# ProPrj_PASSMAN_BLE_Fingerprint_V1_2025-0.net
KiCad netlist of a schematic drawn in EasyEDA Pro
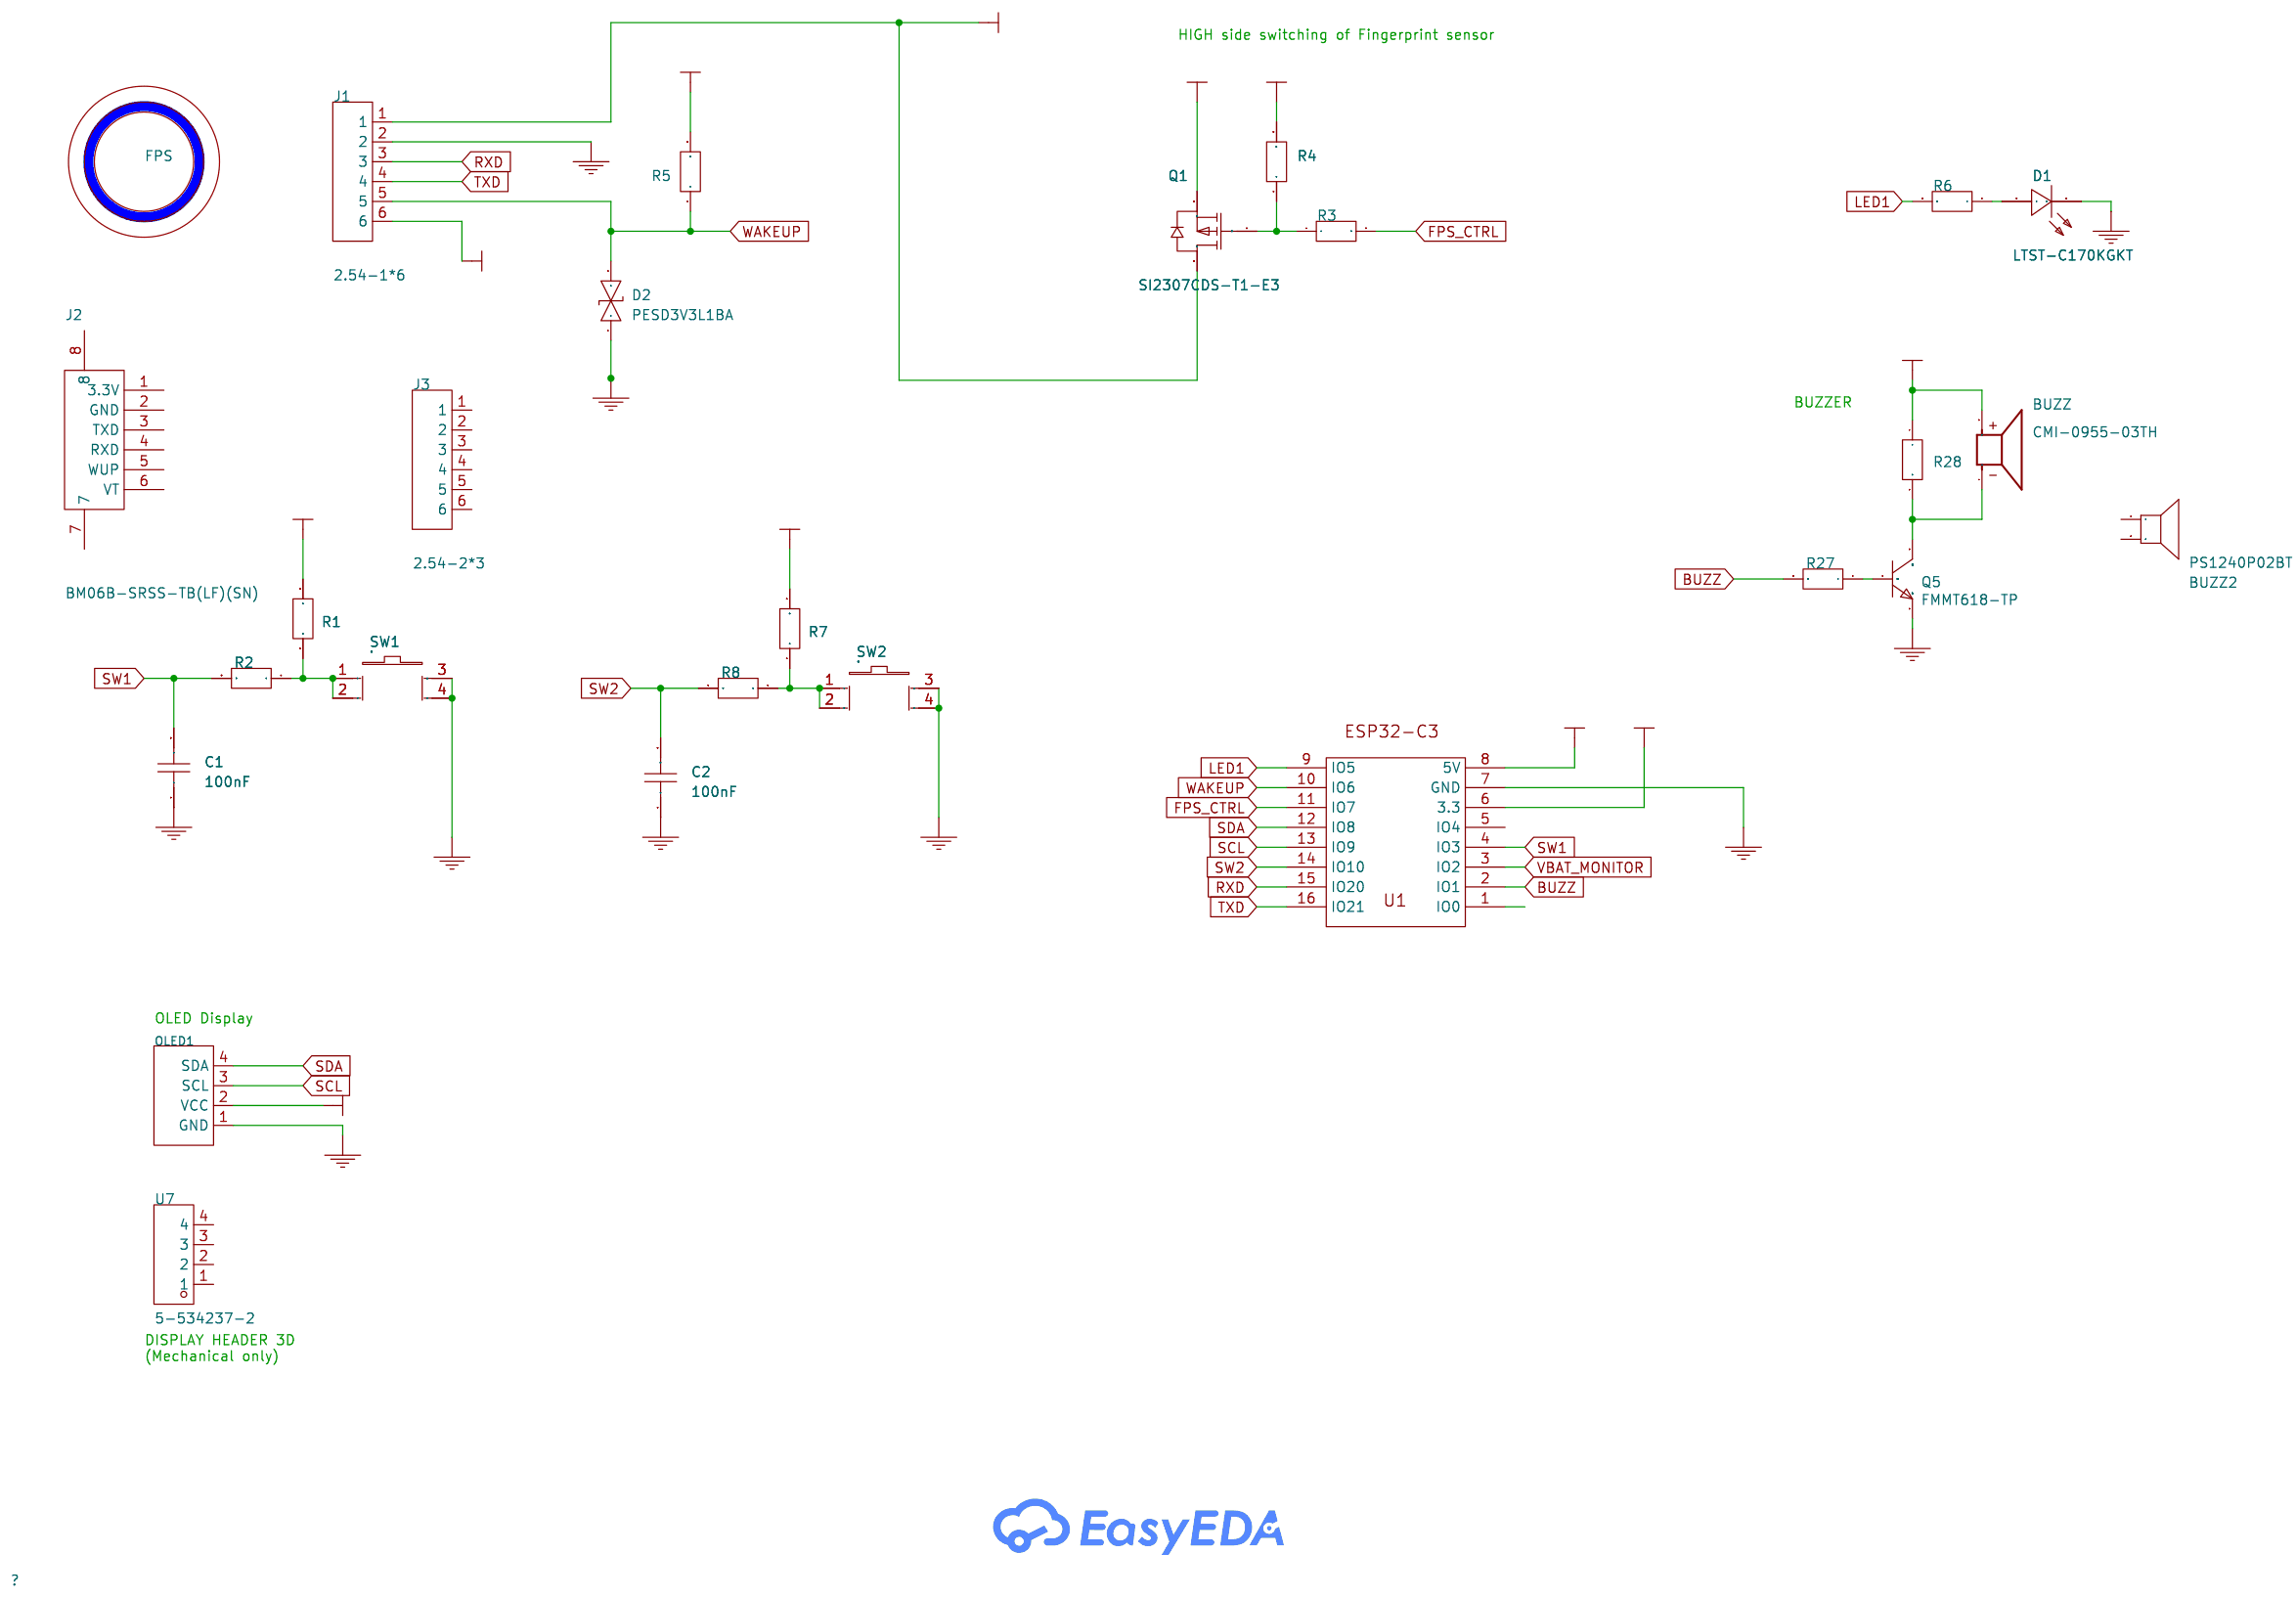
[diagram p0: ESP32 Mini]
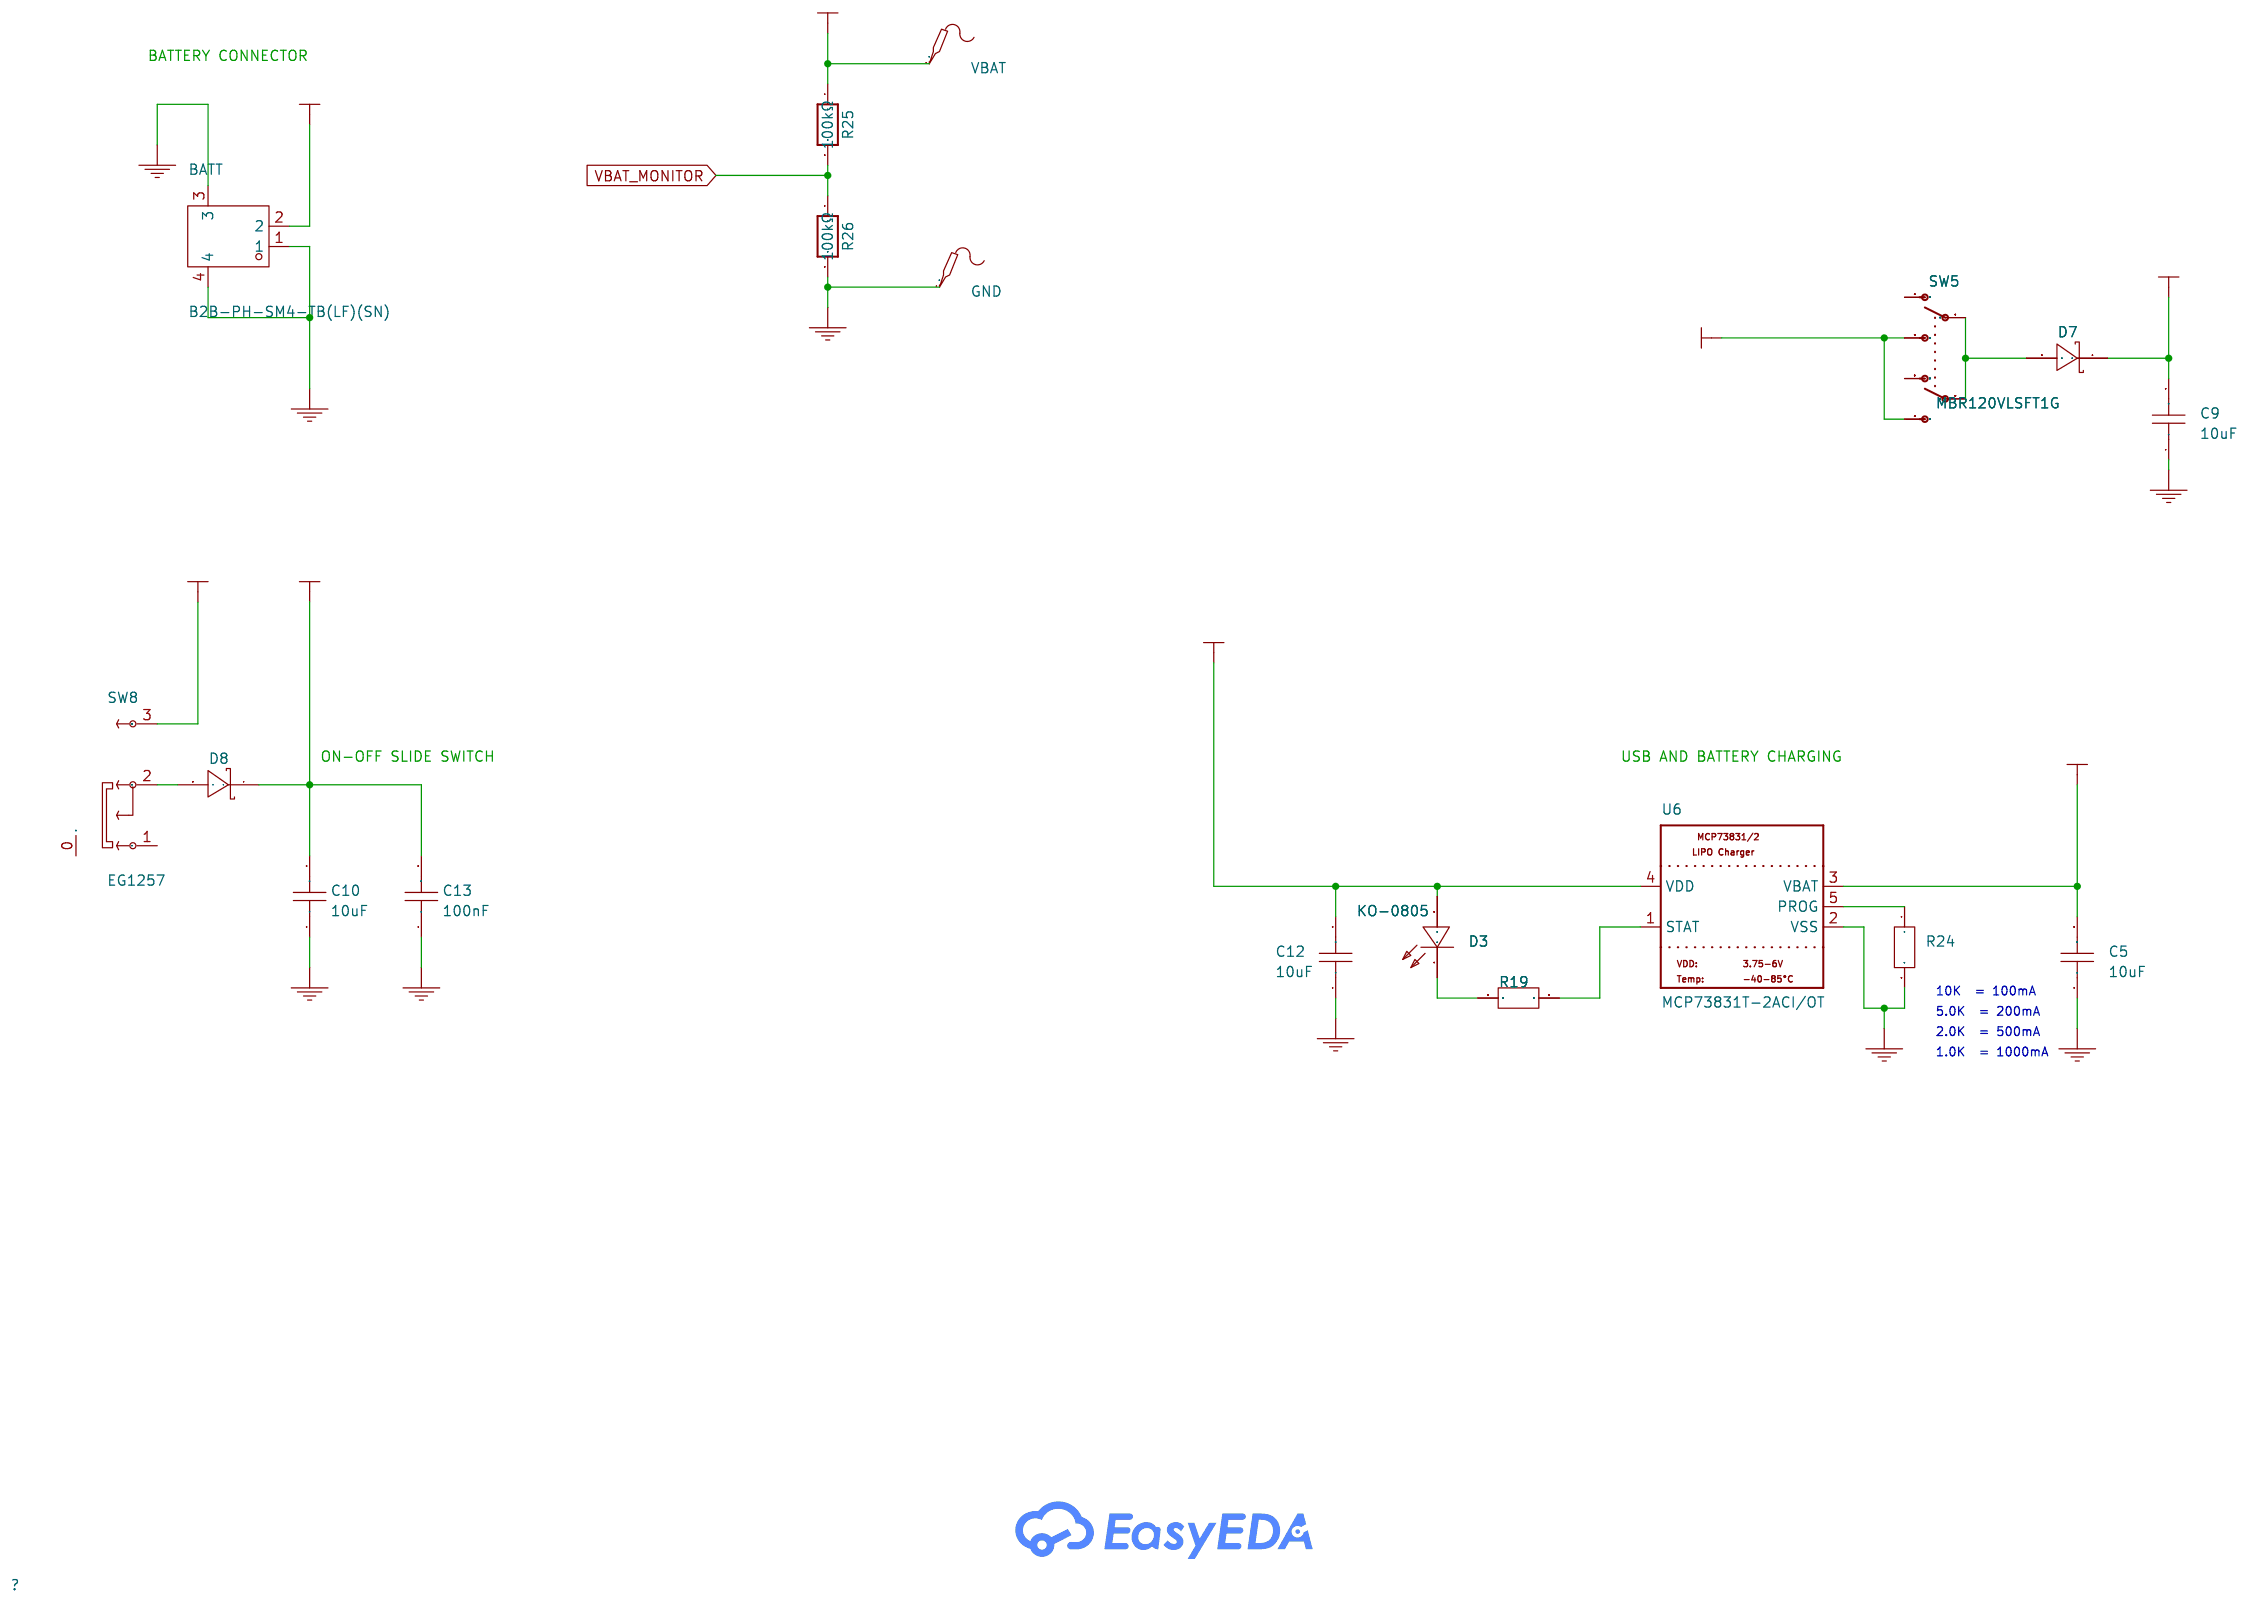
[diagram p1: 2. Battery Man]

(export (version "E")
  (design (tool "Eeschema 10.0.6"))
  (components
    (comp (ref "BUZZ")
      (value "CMI-0955-03TH")
      (footprint "easyedapro:SPKR_CMI-0955-03TH")
      (libsource (lib "easyedapro") (part "CMI-0955-03TH"))
    )
    (comp (ref "BUZZ2")
      (value "PS1240P02BT")
      (footprint "easyedapro:BUZ-TH_BD12.5-P5.00-D0.9")
      (fields (field (name "Manufacturer") "TDK"))
      (libsource (lib "easyedapro") (part "PS1240P02BT"))
    )
    (comp (ref "C1")
      (value "100nF")
      (footprint "easyedapro:C0805")
      (fields
        (field (name "Manufacturer Part") "C2012X7R2A104M125AE")
        (field (name "Manufacturer") "TDK")
        (field (name "Contributor") "lcsc")
      )
      (libsource (lib "easyedapro") (part "100nF"))
    )
    (comp (ref "C2")
      (value "100nF")
      (footprint "easyedapro:C0805")
      (fields
        (field (name "Manufacturer Part") "C2012X7R2A104M125AE")
        (field (name "Manufacturer") "TDK")
        (field (name "Contributor") "lcsc")
      )
      (libsource (lib "easyedapro") (part "100nF"))
    )
    (comp (ref "D1")
      (value "LTST-C170KGKT")
      (footprint "easyedapro:LED0805-RD")
      (fields (field (name "Manufacturer") "LITEON(光宝)"))
      (libsource (lib "easyedapro") (part "KO-0805_C9900066565"))
    )
    (comp (ref "D2")
      (value "PESD3V3L1BA")
      (footprint "easyedapro:SOD-323_L1.8-W1.3-LS2.5-BI")
      (fields (field (name "Manufacturer") "HXY MOSFET(华轩阳电子)"))
      (libsource (lib "easyedapro") (part "PESD3V3L1BA_C5261082"))
    )
    (comp (ref "FPS1")
      (value "FPS")
      (footprint "easyedapro:Fingerprint Sensor 503")
      (description "Fingerprint sensor")
      (libsource (lib "easyedapro") (part "R503 Fingerprint Sensor"))
    )
    (comp (ref "J1")
      (value "2.54-1*6")
      (footprint "easyedapro:HDR-TH_6P-P2.54-V-M")
      (description "Pin Structure:1x6P Pitch:2.54mm Number of Rows:Single Row Number of Pins:6P")
      (fields (field (name "Manufacturer") "ZHOURI(洲日)"))
      (libsource (lib "easyedapro") (part "2.54-1*6"))
    )
    (comp (ref "J2")
      (value "BM06B-SRSS-TB(LF)(SN)")
      (footprint "easyedapro:CONN-SMD-6P-P1.00_BM06B-SRSS-TB-LF-SN")
      (fields (field (name "Manufacturer") "JST"))
      (libsource (lib "easyedapro") (part "BM06B-SRSS-TB(LF)(SN)"))
    )
    (comp (ref "J3")
      (value "2.54-2*3")
      (footprint "easyedapro:HDR-TH_6P-P2.54-V-M")
      (description "Pin Structure:2x3P Pitch:2.54mm Number of Rows:Double Row Number of Pins:6P")
      (fields (field (name "Manufacturer") "ZHOURI(洲日)"))
      (libsource (lib "easyedapro") (part "2.54-1*6"))
    )
    (comp (ref "OLED1")
      (value "HS91L02W2C01")
      (footprint "easyedapro:OLED-TH_L38.0-W12.0_HS91L02W2C01")
      (fields (field (name "Manufacturer") "HS(汉昇)"))
      (libsource (lib "easyedapro") (part "HS91L02W2C01"))
    )
    (comp (ref "Q1")
      (value "SI2307CDS-T1-E3")
      (footprint "easyedapro:SOT-23-3_L2.9-W1.3-P0.95-LS2.4-BR")
      (fields (field (name "Manufacturer") "VISHAY"))
      (libsource (lib "easyedapro") (part "FDN340P_C3277832"))
    )
    (comp (ref "Q5")
      (value "FMMT618-TP")
      (footprint "easyedapro:SOT-23-3_L2.9-W1.3-P0.95-LS2.4-BR")
      (fields (field (name "Manufacturer") "MCC(美微科)") (field (name "Contributor") "LCSC"))
      (libsource (lib "easyedapro") (part "FMMT618-TP"))
    )
    (comp (ref "R1")
      (value "10K")
      (footprint "easyedapro:R0805")
      (fields (field (name "Contributor") "LCSC"))
      (libsource (lib "easyedapro") (part "RES 0805"))
    )
    (comp (ref "R2")
      (value "2K")
      (footprint "easyedapro:R0805")
      (fields (field (name "Contributor") "LCSC"))
      (libsource (lib "easyedapro") (part "RES 0805"))
    )
    (comp (ref "R3")
      (value "10K")
      (footprint "easyedapro:R0805")
      (fields (field (name "Contributor") "LCSC"))
      (libsource (lib "easyedapro") (part "RES 0805"))
    )
    (comp (ref "R4")
      (value "10K")
      (footprint "easyedapro:R0805")
      (fields (field (name "Contributor") "LCSC"))
      (libsource (lib "easyedapro") (part "RES 0805"))
    )
    (comp (ref "R5")
      (value "10K")
      (footprint "easyedapro:R0805")
      (fields (field (name "Contributor") "LCSC"))
      (libsource (lib "easyedapro") (part "RES 0805"))
    )
    (comp (ref "R6")
      (value "470Ω")
      (footprint "easyedapro:R0805")
      (libsource (lib "easyedapro") (part "RES 0805"))
    )
    (comp (ref "R7")
      (value "10K")
      (footprint "easyedapro:R0805")
      (fields (field (name "Contributor") "LCSC"))
      (libsource (lib "easyedapro") (part "RES 0805"))
    )
    (comp (ref "R8")
      (value "2K")
      (footprint "easyedapro:R0805")
      (fields (field (name "Contributor") "LCSC"))
      (libsource (lib "easyedapro") (part "RES 0805"))
    )
    (comp (ref "R27")
      (value "2K")
      (footprint "easyedapro:R0805")
      (fields (field (name "Contributor") "LCSC"))
      (libsource (lib "easyedapro") (part "RES 0805"))
    )
    (comp (ref "R28")
      (value "2K")
      (footprint "easyedapro:R0805")
      (fields (field (name "Contributor") "LCSC"))
      (libsource (lib "easyedapro") (part "RES 0805"))
    )
    (comp (ref "SW1")
      (value ".")
      (footprint "easyedapro:KEY-TH_4P-L6.0-W6.0-P4.50")
      (fields (field (name "Manufacturer Part") "button6*6*8.5") (field (name "Manufacturer") "ReliaPro"))
      (libsource (lib "easyedapro") (part "."))
    )
    (comp (ref "SW2")
      (value ".")
      (footprint "easyedapro:KEY-TH_4P-L6.0-W6.0-P4.50")
      (fields (field (name "Manufacturer Part") "button6*6*8.5") (field (name "Manufacturer") "ReliaPro"))
      (libsource (lib "easyedapro") (part "."))
    )
    (comp (ref "U1")
      (value "ESP32-C3")
      (footprint "easyedapro:ESP32-C3 SUPERMINI TIPO C")
      (fields (field (name "Contributor") "atim.ipn.cet"))
      (libsource (lib "easyedapro") (part "ESP32-C3"))
    )
    (comp (ref "U7")
      (value "5-534237-2")
      (footprint "easyedapro:HDR-TH_8P-P2.54-V-F_5-534237-2")
      (fields (field (name "Manufacturer") "TE Connectivity(泰科电子)"))
      (libsource (lib "easyedapro") (part "5-534237-2"))
    )
    (comp (ref "BATT")
      (value "B2B-PH-SM4-TB(LF)(SN)")
      (footprint "easyedapro:CONN-SMD_B2B-PH-SM4-TB-LF-SN")
      (fields (field (name "Manufacturer") "JST"))
      (libsource (lib "easyedapro") (part "B2B-PH-SM4-TB (LF)(SN)"))
    )
    (comp (ref "C5")
      (value "10uF")
      (footprint "easyedapro:C0805")
      (fields
        (field (name "Manufacturer Part") "C0805X106K9RACTUC0805X106K9RACTU")
        (field (name "Manufacturer") "KEMET")
        (field (name "Contributor") "lcsc")
      )
      (libsource (lib "easyedapro") (part "100nF"))
    )
    (comp (ref "C9")
      (value "10uF")
      (footprint "easyedapro:C0805")
      (fields
        (field (name "Manufacturer Part") "C0805X106K9RACTUC0805X106K9RACTU")
        (field (name "Manufacturer") "KEMET")
        (field (name "Contributor") "lcsc")
      )
      (libsource (lib "easyedapro") (part "100nF"))
    )
    (comp (ref "C10")
      (value "10uF")
      (footprint "easyedapro:C0805")
      (fields
        (field (name "Manufacturer Part") "C0805X106K9RACTUC0805X106K9RACTU")
        (field (name "Manufacturer") "KEMET")
        (field (name "Contributor") "lcsc")
      )
      (libsource (lib "easyedapro") (part "100nF"))
    )
    (comp (ref "C12")
      (value "10uF")
      (footprint "easyedapro:C0805")
      (fields
        (field (name "Manufacturer Part") "C0805X106K9RACTUC0805X106K9RACTU")
        (field (name "Manufacturer") "KEMET")
        (field (name "Contributor") "lcsc")
      )
      (libsource (lib "easyedapro") (part "100nF"))
    )
    (comp (ref "C13")
      (value "100nF")
      (footprint "easyedapro:C0805")
      (fields
        (field (name "Manufacturer Part") "C2012X7R2A104M125AE")
        (field (name "Manufacturer") "TDK")
        (field (name "Contributor") "lcsc")
      )
      (libsource (lib "easyedapro") (part "100nF"))
    )
    (comp (ref "D3")
      (value "KO-0805")
      (footprint "easyedapro:LED0805-RD")
      (libsource (lib "easyedapro") (part "KO-0805_C9900066565"))
    )
    (comp (ref "D7")
      (value "MBR120VLSFT1G")
      (footprint "easyedapro:SOD-123F_L2.8-W1.8-LS3.7-RD")
      (fields (field (name "Manufacturer") "onsemi(安森美)"))
      (libsource (lib "easyedapro") (part "MBR120VLSFT1G"))
    )
    (comp (ref "D8")
      (value "MBR120VLSFT1G")
      (footprint "easyedapro:SOD-123F_L2.8-W1.8-LS3.7-RD")
      (fields (field (name "Manufacturer") "onsemi(安森美)"))
      (libsource (lib "easyedapro") (part "MBR120VLSFT1G"))
    )
    (comp (ref "GND")
      (value "~")
      (footprint "easyedapro:Test-Point-0.5mm")
      (description "Test Point 测试点")
      (libsource (lib "easyedapro") (part "Test-Point"))
    )
    (comp (ref "R19")
      (value "5.1kΩ")
      (footprint "easyedapro:R0805")
      (libsource (lib "easyedapro") (part "RES 0805"))
    )
    (comp (ref "R24")
      (value "5.1kΩ")
      (footprint "easyedapro:R0805")
      (libsource (lib "easyedapro") (part "RES 0805"))
    )
    (comp (ref "R25")
      (value "100kΩ")
      (fields (field (name "Manufacturer Part") "RC0805FR-07100KL") (field (name "Manufacturer") "YAGEO(国巨)"))
      (libsource (lib "easyedapro") (part "microbuilder_RESISTOR__0603_NOOUT"))
    )
    (comp (ref "R26")
      (value "100kΩ")
      (fields (field (name "Manufacturer Part") "RC0805FR-07100KL") (field (name "Manufacturer") "YAGEO(国巨)"))
      (libsource (lib "easyedapro") (part "microbuilder_RESISTOR__0603_NOOUT"))
    )
    (comp (ref "SW5")
      (value "SWITCH_DPDTEG1390")
      (libsource (lib "easyedapro") (part "adafruit_electromech_SWITCH_DPDT_EG1390"))
    )
    (comp (ref "SW8")
      (value "EG1257")
      (footprint "easyedapro:SW-SMD_EG1257")
      (fields (field (name "Manufacturer") "E-Switch"))
      (libsource (lib "easyedapro") (part "EG1257"))
    )
    (comp (ref "U6")
      (value "MCP73831T-2ACI/OT")
      (libsource (lib "easyedapro") (part "microbuilder_MCP73831/2_"))
    )
    (comp (ref "VBAT")
      (value "~")
      (footprint "easyedapro:Test-Point-0.5mm")
      (description "Test Point 测试点")
      (libsource (lib "easyedapro") (part "Test-Point"))
    )
  )
  (nets
    (net (code "1") (name "3.3V") (class "Default")
      (node (ref "J1") (pin "6") (pinfunction "6_6") (pintype "unspecified"))
      (node (ref "OLED1") (pin "2") (pinfunction "VCC_2") (pintype "input"))
      (node (ref "Q1") (pin "2") (pinfunction "S_2") (pintype "unspecified"))
      (node (ref "R1") (pin "2") (pinfunction "2_2") (pintype "unspecified"))
      (node (ref "R4") (pin "2") (pinfunction "2_2") (pintype "unspecified"))
      (node (ref "R5") (pin "2") (pinfunction "2_2") (pintype "unspecified"))
      (node (ref "R7") (pin "2") (pinfunction "2_2") (pintype "unspecified"))
      (node (ref "U1") (pin "6") (pinfunction "3.3_6") (pintype "unspecified"))
    )
    (net (code "2") (name "5V") (class "Default")
      (node (ref "C9") (pin "2") (pinfunction "2_2") (pintype "unspecified"))
      (node (ref "D7") (pin "1") (pinfunction "K_1") (pintype "unspecified"))
    )
    (net (code "3") (name "BUZZ") (class "Default")
      (node (ref "R27") (pin "2") (pinfunction "2_2") (pintype "unspecified"))
      (node (ref "U1") (pin "2") (pinfunction "IO1_2") (pintype "unspecified"))
    )
    (net (code "4") (name "FPS_CTRL") (class "Default")
      (node (ref "R3") (pin "2") (pinfunction "2_2") (pintype "unspecified"))
      (node (ref "U1") (pin "11") (pinfunction "IO7_11") (pintype "unspecified"))
    )
    (net (code "5") (name "GND") (class "Default")
      (node (ref "BATT") (pin "1") (pinfunction "1_1") (pintype "unspecified"))
      (node (ref "BATT") (pin "3") (pinfunction "3_3") (pintype "unspecified"))
      (node (ref "BATT") (pin "4") (pinfunction "4_4") (pintype "unspecified"))
      (node (ref "C1") (pin "1") (pinfunction "1_1") (pintype "unspecified"))
      (node (ref "C10") (pin "1") (pinfunction "1_1") (pintype "unspecified"))
      (node (ref "C12") (pin "1") (pinfunction "1_1") (pintype "unspecified"))
      (node (ref "C13") (pin "1") (pinfunction "1_1") (pintype "unspecified"))
      (node (ref "C2") (pin "1") (pinfunction "1_1") (pintype "unspecified"))
      (node (ref "C5") (pin "1") (pinfunction "1_1") (pintype "unspecified"))
      (node (ref "C9") (pin "1") (pinfunction "1_1") (pintype "unspecified"))
      (node (ref "D1") (pin "1") (pinfunction "K_1") (pintype "unspecified"))
      (node (ref "D2") (pin "1") (pinfunction "1_1") (pintype "unspecified"))
      (node (ref "GND") (pin "1") (pinfunction "1_1") (pintype "unspecified"))
      (node (ref "J1") (pin "2") (pinfunction "2_2") (pintype "unspecified"))
      (node (ref "OLED1") (pin "1") (pinfunction "GND_1") (pintype "input"))
      (node (ref "Q5") (pin "2") (pinfunction "EMITTER_2") (pintype "input"))
      (node (ref "R24") (pin "2") (pinfunction "2_2") (pintype "unspecified"))
      (node (ref "R26") (pin "2") (pinfunction "2_2") (pintype "unspecified"))
      (node (ref "SW1") (pin "3") (pinfunction "3_3") (pintype "input"))
      (node (ref "SW1") (pin "4") (pinfunction "4_4") (pintype "input"))
      (node (ref "SW2") (pin "3") (pinfunction "3_3") (pintype "input"))
      (node (ref "SW2") (pin "4") (pinfunction "4_4") (pintype "input"))
      (node (ref "U1") (pin "7") (pinfunction "GND_7") (pintype "unspecified"))
      (node (ref "U6") (pin "2") (pinfunction "VSS_2") (pintype "unspecified"))
    )
    (net (code "6") (name "LED1") (class "Default")
      (node (ref "R6") (pin "2") (pinfunction "2_2") (pintype "unspecified"))
      (node (ref "U1") (pin "9") (pinfunction "IO5_9") (pintype "unspecified"))
    )
    (net (code "7") (name "Net-(D1-A)") (class "Default")
      (node (ref "D1") (pin "2") (pinfunction "A_2") (pintype "unspecified"))
      (node (ref "R6") (pin "1") (pinfunction "1_1") (pintype "unspecified"))
    )
    (net (code "8") (name "Net-(D3-K)") (class "Default")
      (node (ref "D3") (pin "1") (pinfunction "K_1") (pintype "unspecified"))
      (node (ref "R19") (pin "2") (pinfunction "2_2") (pintype "unspecified"))
    )
    (net (code "9") (name "Net-(D7-A)") (class "Default")
      (node (ref "D7") (pin "2") (pinfunction "A_2") (pintype "unspecified"))
      (node (ref "SW5") (pin "P1") (pinfunction "P1_P1") (pintype "unspecified"))
      (node (ref "SW5") (pin "P2") (pinfunction "P2_P2") (pintype "unspecified"))
    )
    (net (code "10") (name "Net-(D8-A)") (class "Default")
      (node (ref "D8") (pin "2") (pinfunction "A_2") (pintype "unspecified"))
      (node (ref "SW8") (pin "2") (pinfunction "2_2") (pintype "unspecified"))
    )
    (net (code "11") (name "Net-(Q1-G)") (class "Default")
      (node (ref "Q1") (pin "1") (pinfunction "G_1") (pintype "unspecified"))
      (node (ref "R3") (pin "1") (pinfunction "1_1") (pintype "unspecified"))
      (node (ref "R4") (pin "1") (pinfunction "1_1") (pintype "unspecified"))
    )
    (net (code "12") (name "Net-(Q5-BASE)") (class "Default")
      (node (ref "Q5") (pin "1") (pinfunction "BASE_1") (pintype "input"))
      (node (ref "R27") (pin "1") (pinfunction "1_1") (pintype "unspecified"))
    )
    (net (code "13") (name "Net-(Q5-COLLECTOR)") (class "Default")
      (node (ref "BUZZ") (pin "N") (pinfunction "N_N") (pintype "unspecified"))
      (node (ref "Q5") (pin "3") (pinfunction "COLLECTOR_3") (pintype "input"))
      (node (ref "R28") (pin "2") (pinfunction "2_2") (pintype "unspecified"))
    )
    (net (code "14") (name "Net-(R1-Pad1)") (class "Default")
      (node (ref "R1") (pin "1") (pinfunction "1_1") (pintype "unspecified"))
      (node (ref "R2") (pin "1") (pinfunction "1_1") (pintype "unspecified"))
      (node (ref "SW1") (pin "1") (pinfunction "1_1") (pintype "input"))
      (node (ref "SW1") (pin "2") (pinfunction "2_2") (pintype "input"))
    )
    (net (code "15") (name "Net-(R7-Pad1)") (class "Default")
      (node (ref "R7") (pin "1") (pinfunction "1_1") (pintype "unspecified"))
      (node (ref "R8") (pin "1") (pinfunction "1_1") (pintype "unspecified"))
      (node (ref "SW2") (pin "1") (pinfunction "1_1") (pintype "input"))
      (node (ref "SW2") (pin "2") (pinfunction "2_2") (pintype "input"))
    )
    (net (code "16") (name "Net-(U6-PROG)") (class "Default")
      (node (ref "R24") (pin "1") (pinfunction "1_1") (pintype "unspecified"))
      (node (ref "U6") (pin "5") (pinfunction "PROG_5") (pintype "input"))
    )
    (net (code "17") (name "Net-(U6-STAT)") (class "Default")
      (node (ref "R19") (pin "1") (pinfunction "1_1") (pintype "unspecified"))
      (node (ref "U6") (pin "1") (pinfunction "STAT_1") (pintype "output"))
    )
    (net (code "18") (name "RXD") (class "Default")
      (node (ref "J1") (pin "3") (pinfunction "3_3") (pintype "unspecified"))
      (node (ref "U1") (pin "15") (pinfunction "IO20_15") (pintype "unspecified"))
    )
    (net (code "19") (name "SCL") (class "Default")
      (node (ref "OLED1") (pin "3") (pinfunction "SCL_3") (pintype "input"))
      (node (ref "U1") (pin "13") (pinfunction "IO9_13") (pintype "unspecified"))
    )
    (net (code "20") (name "SDA") (class "Default")
      (node (ref "OLED1") (pin "4") (pinfunction "SDA_4") (pintype "input"))
      (node (ref "U1") (pin "12") (pinfunction "IO8_12") (pintype "unspecified"))
    )
    (net (code "21") (name "SW1") (class "Default")
      (node (ref "C1") (pin "2") (pinfunction "2_2") (pintype "unspecified"))
      (node (ref "R2") (pin "2") (pinfunction "2_2") (pintype "unspecified"))
      (node (ref "U1") (pin "4") (pinfunction "IO3_4") (pintype "unspecified"))
    )
    (net (code "22") (name "SW2") (class "Default")
      (node (ref "C2") (pin "2") (pinfunction "2_2") (pintype "unspecified"))
      (node (ref "R8") (pin "2") (pinfunction "2_2") (pintype "unspecified"))
      (node (ref "U1") (pin "14") (pinfunction "IO10_14") (pintype "unspecified"))
    )
    (net (code "23") (name "TXD") (class "Default")
      (node (ref "J1") (pin "4") (pinfunction "4_4") (pintype "unspecified"))
      (node (ref "U1") (pin "16") (pinfunction "IO21_16") (pintype "unspecified"))
    )
    (net (code "24") (name "VBAT") (class "Default")
      (node (ref "BATT") (pin "2") (pinfunction "2_2") (pintype "unspecified"))
      (node (ref "C5") (pin "2") (pinfunction "2_2") (pintype "unspecified"))
      (node (ref "SW5") (pin "S1") (pinfunction "S1_S1") (pintype "unspecified"))
      (node (ref "SW5") (pin "S2") (pinfunction "S2_S2") (pintype "unspecified"))
      (node (ref "SW8") (pin "3") (pinfunction "3_3") (pintype "unspecified"))
      (node (ref "U6") (pin "3") (pinfunction "VBAT_3") (pintype "unspecified"))
    )
    (net (code "25") (name "VBAT_MONITOR") (class "Default")
      (node (ref "R25") (pin "2") (pinfunction "2_2") (pintype "unspecified"))
      (node (ref "R26") (pin "1") (pinfunction "1_1") (pintype "unspecified"))
      (node (ref "U1") (pin "3") (pinfunction "IO2_3") (pintype "unspecified"))
    )
    (net (code "26") (name "VCC_FPS") (class "Default")
      (node (ref "J1") (pin "1") (pinfunction "1_1") (pintype "unspecified"))
      (node (ref "Q1") (pin "3") (pinfunction "D_3") (pintype "unspecified"))
    )
    (net (code "27") (name "V_PIN8_ESP32") (class "Default")
      (node (ref "BUZZ") (pin "P") (pinfunction "P_P") (pintype "unspecified"))
      (node (ref "C10") (pin "2") (pinfunction "2_2") (pintype "unspecified"))
      (node (ref "C12") (pin "2") (pinfunction "2_2") (pintype "unspecified"))
      (node (ref "C13") (pin "2") (pinfunction "2_2") (pintype "unspecified"))
      (node (ref "D3") (pin "2") (pinfunction "A_2") (pintype "unspecified"))
      (node (ref "D8") (pin "1") (pinfunction "K_1") (pintype "unspecified"))
      (node (ref "R25") (pin "1") (pinfunction "1_1") (pintype "unspecified"))
      (node (ref "R28") (pin "1") (pinfunction "1_1") (pintype "unspecified"))
      (node (ref "U1") (pin "8") (pinfunction "5V_8") (pintype "unspecified"))
      (node (ref "U6") (pin "4") (pinfunction "VDD_4") (pintype "unspecified"))
      (node (ref "VBAT") (pin "1") (pinfunction "1_1") (pintype "unspecified"))
    )
    (net (code "28") (name "WAKEUP") (class "Default")
      (node (ref "D2") (pin "2") (pinfunction "2_2") (pintype "unspecified"))
      (node (ref "J1") (pin "5") (pinfunction "5_5") (pintype "unspecified"))
      (node (ref "R5") (pin "1") (pinfunction "1_1") (pintype "unspecified"))
      (node (ref "U1") (pin "10") (pinfunction "IO6_10") (pintype "unspecified"))
    )
    (net (code "29") (name "unconnected-(BUZZ2-Pad1)") (class "Default")
      (node (ref "BUZZ2") (pin "1") (pinfunction "1_1") (pintype "unspecified"))
    )
    (net (code "30") (name "unconnected-(BUZZ2-Pad2)") (class "Default")
      (node (ref "BUZZ2") (pin "2") (pinfunction "2_2") (pintype "unspecified"))
    )
    (net (code "31") (name "unconnected-(J2-3.3V-Pad1)") (class "Default")
      (node (ref "J2") (pin "1") (pinfunction "3.3V_1") (pintype "unspecified"))
    )
    (net (code "32") (name "unconnected-(J2-GND-Pad2)") (class "Default")
      (node (ref "J2") (pin "2") (pinfunction "GND_2") (pintype "unspecified"))
    )
    (net (code "33") (name "unconnected-(J2-Pad7)") (class "Default")
      (node (ref "J2") (pin "7") (pinfunction "7_7") (pintype "unspecified"))
    )
    (net (code "34") (name "unconnected-(J2-Pad8)") (class "Default")
      (node (ref "J2") (pin "8") (pinfunction "8_8") (pintype "unspecified"))
    )
    (net (code "35") (name "unconnected-(J2-RXD-Pad4)") (class "Default")
      (node (ref "J2") (pin "4") (pinfunction "RXD_4") (pintype "unspecified"))
    )
    (net (code "36") (name "unconnected-(J2-TXD-Pad3)") (class "Default")
      (node (ref "J2") (pin "3") (pinfunction "TXD_3") (pintype "unspecified"))
    )
    (net (code "37") (name "unconnected-(J2-VT-Pad6)") (class "Default")
      (node (ref "J2") (pin "6") (pinfunction "VT_6") (pintype "unspecified"))
    )
    (net (code "38") (name "unconnected-(J2-WUP-Pad5)") (class "Default")
      (node (ref "J2") (pin "5") (pinfunction "WUP_5") (pintype "unspecified"))
    )
    (net (code "39") (name "unconnected-(J3-Pad1)") (class "Default")
      (node (ref "J3") (pin "1") (pinfunction "1_1") (pintype "unspecified"))
    )
    (net (code "40") (name "unconnected-(J3-Pad2)") (class "Default")
      (node (ref "J3") (pin "2") (pinfunction "2_2") (pintype "unspecified"))
    )
    (net (code "41") (name "unconnected-(J3-Pad3)") (class "Default")
      (node (ref "J3") (pin "3") (pinfunction "3_3") (pintype "unspecified"))
    )
    (net (code "42") (name "unconnected-(J3-Pad4)") (class "Default")
      (node (ref "J3") (pin "4") (pinfunction "4_4") (pintype "unspecified"))
    )
    (net (code "43") (name "unconnected-(J3-Pad5)") (class "Default")
      (node (ref "J3") (pin "5") (pinfunction "5_5") (pintype "unspecified"))
    )
    (net (code "44") (name "unconnected-(J3-Pad6)") (class "Default")
      (node (ref "J3") (pin "6") (pinfunction "6_6") (pintype "unspecified"))
    )
    (net (code "45") (name "unconnected-(SW5-PadO1)") (class "Default")
      (node (ref "SW5") (pin "O1") (pinfunction "O1_O1") (pintype "unspecified"))
    )
    (net (code "46") (name "unconnected-(SW5-PadO2)") (class "Default")
      (node (ref "SW5") (pin "O2") (pinfunction "O2_O2") (pintype "unspecified"))
    )
    (net (code "47") (name "unconnected-(SW8-EH-Pad0)") (class "Default")
      (node (ref "SW8") (pin "0") (pinfunction "EH_0") (pintype "unspecified"))
    )
    (net (code "48") (name "unconnected-(SW8-Pad1)") (class "Default")
      (node (ref "SW8") (pin "1") (pinfunction "1_1") (pintype "unspecified"))
    )
    (net (code "49") (name "unconnected-(U1-IO0-Pad1)") (class "Default")
      (node (ref "U1") (pin "1") (pinfunction "IO0_1") (pintype "unspecified"))
    )
    (net (code "50") (name "unconnected-(U1-IO4-Pad5)") (class "Default")
      (node (ref "U1") (pin "5") (pinfunction "IO4_5") (pintype "unspecified"))
    )
    (net (code "51") (name "unconnected-(U7-Pad1)") (class "Default")
      (node (ref "U7") (pin "1") (pinfunction "1_1") (pintype "unspecified"))
    )
    (net (code "52") (name "unconnected-(U7-Pad2)") (class "Default")
      (node (ref "U7") (pin "2") (pinfunction "2_2") (pintype "unspecified"))
    )
    (net (code "53") (name "unconnected-(U7-Pad3)") (class "Default")
      (node (ref "U7") (pin "3") (pinfunction "3_3") (pintype "unspecified"))
    )
    (net (code "54") (name "unconnected-(U7-Pad4)") (class "Default")
      (node (ref "U7") (pin "4") (pinfunction "4_4") (pintype "unspecified"))
    )
  )
)
